# power.net
KiCad netlist of a schematic drawn in EAGLE
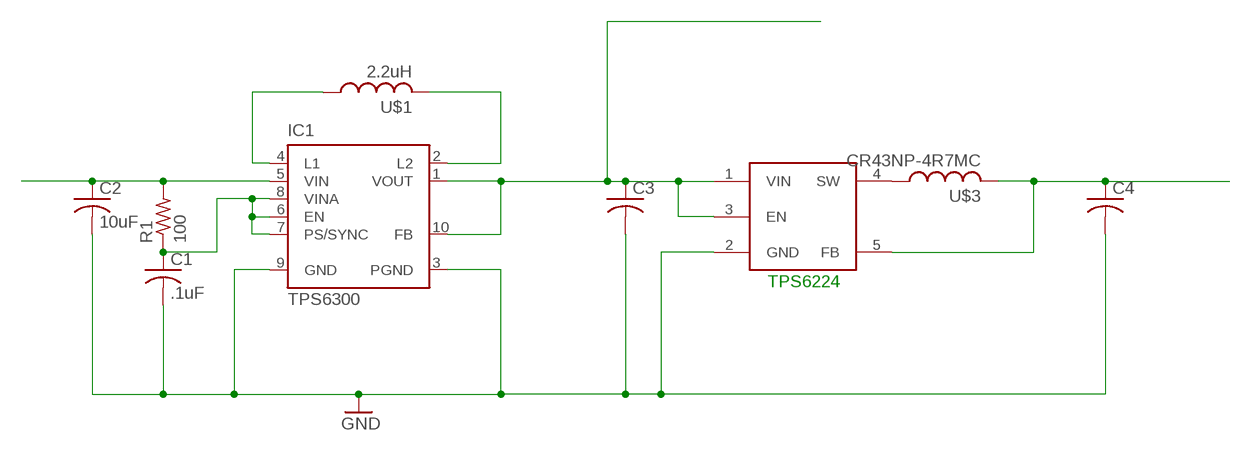
[diagram p0: schematic, sheet 1]

(export (version "E")
  (design (tool "Eeschema 10.0.6"))
  (components
    (comp (ref "C1")
      (value ".1uF")
      (footprint "eagle-import:C0603")
      (libsource (lib "eagle-import") (part "C-USC0603"))
    )
    (comp (ref "C2")
      (value "10uF")
      (footprint "eagle-import:C0603")
      (libsource (lib "eagle-import") (part "C-USC0603"))
    )
    (comp (ref "C3")
      (value "C-USC0805")
      (footprint "eagle-import:C0805")
      (libsource (lib "eagle-import") (part "C-USC0805"))
    )
    (comp (ref "C4")
      (value "C-USC1210")
      (footprint "eagle-import:C1210")
      (libsource (lib "eagle-import") (part "C-USC1210"))
    )
    (comp (ref "IC1")
      (value "TPS6300")
      (footprint "eagle-import:DRC-S-PVSON-N10")
      (fields (field (name "MPN") "TPS63000DRCTG4"))
      (libsource (lib "eagle-import") (part "TPS6300"))
    )
    (comp (ref "R1")
      (value "100")
      (footprint "eagle-import:R01005")
      (libsource (lib "eagle-import") (part "R-US_01005"))
    )
    (comp (ref "U$1")
      (value "2.2uH")
      (footprint "eagle-import:INDUCTOR")
      (libsource (lib "eagle-import") (part "VLS4012"))
    )
    (comp (ref "U$2")
      (value "TPS62240")
      (footprint "eagle-import:TSP62240")
      (libsource (lib "eagle-import") (part "TPS62240"))
    )
    (comp (ref "U$3")
      (value "CR43NP-4R7MC")
      (footprint "eagle-import:INDUCTOR")
      (libsource (lib "eagle-import") (part "CR43NP-4R7MC"))
    )
  )
  (nets
    (net (code "1") (name "GND") (class "Default")
      (node (ref "C1") (pin "2") (pinfunction "2_2") (pintype "passive"))
      (node (ref "C2") (pin "2") (pinfunction "2_2") (pintype "passive"))
      (node (ref "C3") (pin "2") (pinfunction "2_2") (pintype "passive"))
      (node (ref "C4") (pin "2") (pinfunction "2_2") (pintype "passive"))
      (node (ref "IC1") (pin "3") (pinfunction "PGND_3") (pintype "power_in"))
      (node (ref "IC1") (pin "9") (pinfunction "GND_9") (pintype "power_in"))
      (node (ref "U$2") (pin "2") (pinfunction "GND_2") (pintype "bidirectional"))
    )
    (net (code "2") (name "Net-(IC1A-EN)") (class "Default")
      (node (ref "C1") (pin "1") (pinfunction "1_1") (pintype "passive"))
      (node (ref "IC1") (pin "6") (pinfunction "EN_6") (pintype "input"))
      (node (ref "IC1") (pin "7") (pinfunction "PS/SYNC_7") (pintype "input"))
      (node (ref "IC1") (pin "8") (pinfunction "VINA_8") (pintype "input"))
      (node (ref "R1") (pin "1") (pinfunction "1_1") (pintype "passive"))
    )
    (net (code "3") (name "Net-(IC1A-FB)") (class "Default")
      (node (ref "C3") (pin "1") (pinfunction "1_1") (pintype "passive"))
      (node (ref "IC1") (pin "1") (pinfunction "VOUT_1") (pintype "output"))
      (node (ref "IC1") (pin "10") (pinfunction "FB_10") (pintype "input"))
      (node (ref "U$2") (pin "1") (pinfunction "VIN_1") (pintype "bidirectional"))
      (node (ref "U$2") (pin "3") (pinfunction "EN_3") (pintype "bidirectional"))
    )
    (net (code "4") (name "Net-(IC1A-L1)") (class "Default")
      (node (ref "IC1") (pin "4") (pinfunction "L1_4") (pintype "passive"))
      (node (ref "U$1") (pin "P$1") (pinfunction "1_P$1") (pintype "passive"))
    )
    (net (code "5") (name "Net-(IC1A-L2)") (class "Default")
      (node (ref "IC1") (pin "2") (pinfunction "L2_2") (pintype "passive"))
      (node (ref "U$1") (pin "P$2") (pinfunction "2_P$2") (pintype "passive"))
    )
    (net (code "6") (name "Net-(IC1A-VIN)") (class "Default")
      (node (ref "C2") (pin "1") (pinfunction "1_1") (pintype "passive"))
      (node (ref "IC1") (pin "5") (pinfunction "VIN_5") (pintype "input"))
      (node (ref "R1") (pin "2") (pinfunction "2_2") (pintype "passive"))
    )
    (net (code "7") (name "Net-(U$2-FB)") (class "Default")
      (node (ref "C4") (pin "1") (pinfunction "1_1") (pintype "passive"))
      (node (ref "U$2") (pin "5") (pinfunction "FB_5") (pintype "bidirectional"))
      (node (ref "U$3") (pin "P$2") (pinfunction "2_P$2") (pintype "passive"))
    )
    (net (code "8") (name "Net-(U$2-SW)") (class "Default")
      (node (ref "U$2") (pin "4") (pinfunction "SW_4") (pintype "bidirectional"))
      (node (ref "U$3") (pin "P$1") (pinfunction "1_P$1") (pintype "passive"))
    )
  )
)
